# Accumulator_HotDog_v2.net
KiCad netlist of a schematic drawn in Altium Designer
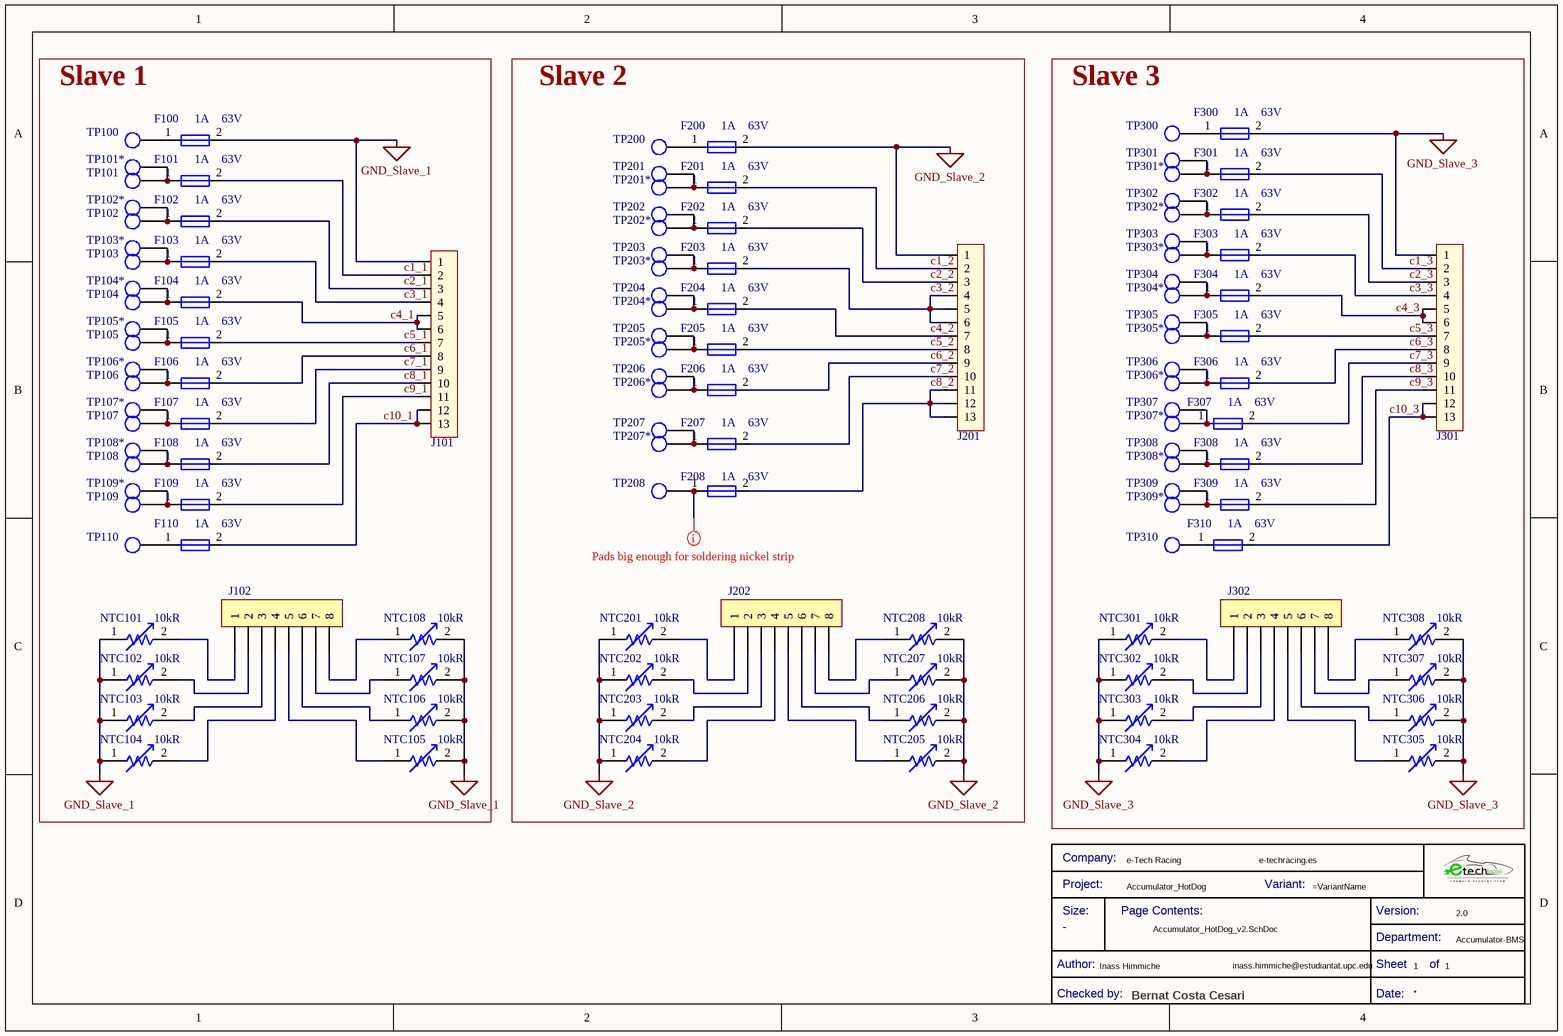
[diagram p0: Accumulator_HotDog_v2.SchDoc]

(export (version "E")
  (design (tool "Eeschema 10.0.6"))
  (components
    (comp (ref "*")
      (value "Title Block_template")
      (description "Standard Title Block")
      (fields (field (name "SIZE") "-"))
      (libsource (lib "e-Tech_Racing") (part "Title Block_template"))
    )
    (comp (ref "F100")
      (value "0437001.WRA")
      (footprint "Fuse_1206")
      (description "Fuse Chip Fast Acting 1A 63V SMD Solder Pad 1206 Ceramic T/R Automotive")
      (fields
        (field (name "MANUFACTURER") "Littelfuse")
        (field (name "CURRENT RATING") "1A")
        (field (name "VOLTAGE RATING (DC)") "63V")
      )
      (libsource (lib "Filter components") (part "Fuse_1A_63V_1206"))
    )
    (comp (ref "F101")
      (value "0437001.WRA")
      (footprint "Fuse_1206")
      (description "Fuse Chip Fast Acting 1A 63V SMD Solder Pad 1206 Ceramic T/R Automotive")
      (fields
        (field (name "MANUFACTURER") "Littelfuse")
        (field (name "CURRENT RATING") "1A")
        (field (name "VOLTAGE RATING (DC)") "63V")
      )
      (libsource (lib "Filter components") (part "Fuse_1A_63V_1206"))
    )
    (comp (ref "F102")
      (value "0437001.WRA")
      (footprint "Fuse_1206")
      (description "Fuse Chip Fast Acting 1A 63V SMD Solder Pad 1206 Ceramic T/R Automotive")
      (fields
        (field (name "MANUFACTURER") "Littelfuse")
        (field (name "CURRENT RATING") "1A")
        (field (name "VOLTAGE RATING (DC)") "63V")
      )
      (libsource (lib "Filter components") (part "Fuse_1A_63V_1206"))
    )
    (comp (ref "F103")
      (value "0437001.WRA")
      (footprint "Fuse_1206")
      (description "Fuse Chip Fast Acting 1A 63V SMD Solder Pad 1206 Ceramic T/R Automotive")
      (fields
        (field (name "MANUFACTURER") "Littelfuse")
        (field (name "CURRENT RATING") "1A")
        (field (name "VOLTAGE RATING (DC)") "63V")
      )
      (libsource (lib "Filter components") (part "Fuse_1A_63V_1206"))
    )
    (comp (ref "F104")
      (value "0437001.WRA")
      (footprint "Fuse_1206")
      (description "Fuse Chip Fast Acting 1A 63V SMD Solder Pad 1206 Ceramic T/R Automotive")
      (fields
        (field (name "MANUFACTURER") "Littelfuse")
        (field (name "CURRENT RATING") "1A")
        (field (name "VOLTAGE RATING (DC)") "63V")
      )
      (libsource (lib "Filter components") (part "Fuse_1A_63V_1206"))
    )
    (comp (ref "F105")
      (value "0437001.WRA")
      (footprint "Fuse_1206")
      (description "Fuse Chip Fast Acting 1A 63V SMD Solder Pad 1206 Ceramic T/R Automotive")
      (fields
        (field (name "MANUFACTURER") "Littelfuse")
        (field (name "CURRENT RATING") "1A")
        (field (name "VOLTAGE RATING (DC)") "63V")
      )
      (libsource (lib "Filter components") (part "Fuse_1A_63V_1206"))
    )
    (comp (ref "F106")
      (value "0437001.WRA")
      (footprint "Fuse_1206")
      (description "Fuse Chip Fast Acting 1A 63V SMD Solder Pad 1206 Ceramic T/R Automotive")
      (fields
        (field (name "MANUFACTURER") "Littelfuse")
        (field (name "CURRENT RATING") "1A")
        (field (name "VOLTAGE RATING (DC)") "63V")
      )
      (libsource (lib "Filter components") (part "Fuse_1A_63V_1206"))
    )
    (comp (ref "F107")
      (value "0437001.WRA")
      (footprint "Fuse_1206")
      (description "Fuse Chip Fast Acting 1A 63V SMD Solder Pad 1206 Ceramic T/R Automotive")
      (fields
        (field (name "MANUFACTURER") "Littelfuse")
        (field (name "CURRENT RATING") "1A")
        (field (name "VOLTAGE RATING (DC)") "63V")
      )
      (libsource (lib "Filter components") (part "Fuse_1A_63V_1206"))
    )
    (comp (ref "F108")
      (value "0437001.WRA")
      (footprint "Fuse_1206")
      (description "Fuse Chip Fast Acting 1A 63V SMD Solder Pad 1206 Ceramic T/R Automotive")
      (fields
        (field (name "MANUFACTURER") "Littelfuse")
        (field (name "CURRENT RATING") "1A")
        (field (name "VOLTAGE RATING (DC)") "63V")
      )
      (libsource (lib "Filter components") (part "Fuse_1A_63V_1206"))
    )
    (comp (ref "F109")
      (value "0437001.WRA")
      (footprint "Fuse_1206")
      (description "Fuse Chip Fast Acting 1A 63V SMD Solder Pad 1206 Ceramic T/R Automotive")
      (fields
        (field (name "MANUFACTURER") "Littelfuse")
        (field (name "CURRENT RATING") "1A")
        (field (name "VOLTAGE RATING (DC)") "63V")
      )
      (libsource (lib "Filter components") (part "Fuse_1A_63V_1206"))
    )
    (comp (ref "F110")
      (value "0437001.WRA")
      (footprint "Fuse_1206")
      (description "Fuse Chip Fast Acting 1A 63V SMD Solder Pad 1206 Ceramic T/R Automotive")
      (fields
        (field (name "MANUFACTURER") "Littelfuse")
        (field (name "CURRENT RATING") "1A")
        (field (name "VOLTAGE RATING (DC)") "63V")
      )
      (libsource (lib "Filter components") (part "Fuse_1A_63V_1206"))
    )
    (comp (ref "F200")
      (value "0437001.WRA")
      (footprint "Fuse_1206")
      (description "Fuse Chip Fast Acting 1A 63V SMD Solder Pad 1206 Ceramic T/R Automotive")
      (fields
        (field (name "MANUFACTURER") "Littelfuse")
        (field (name "CURRENT RATING") "1A")
        (field (name "VOLTAGE RATING (DC)") "63V")
      )
      (libsource (lib "Filter components") (part "Fuse_1A_63V_1206"))
    )
    (comp (ref "F201")
      (value "0437001.WRA")
      (footprint "Fuse_1206")
      (description "Fuse Chip Fast Acting 1A 63V SMD Solder Pad 1206 Ceramic T/R Automotive")
      (fields
        (field (name "MANUFACTURER") "Littelfuse")
        (field (name "CURRENT RATING") "1A")
        (field (name "VOLTAGE RATING (DC)") "63V")
      )
      (libsource (lib "Filter components") (part "Fuse_1A_63V_1206"))
    )
    (comp (ref "F202")
      (value "0437001.WRA")
      (footprint "Fuse_1206")
      (description "Fuse Chip Fast Acting 1A 63V SMD Solder Pad 1206 Ceramic T/R Automotive")
      (fields
        (field (name "MANUFACTURER") "Littelfuse")
        (field (name "CURRENT RATING") "1A")
        (field (name "VOLTAGE RATING (DC)") "63V")
      )
      (libsource (lib "Filter components") (part "Fuse_1A_63V_1206"))
    )
    (comp (ref "F203")
      (value "0437001.WRA")
      (footprint "Fuse_1206")
      (description "Fuse Chip Fast Acting 1A 63V SMD Solder Pad 1206 Ceramic T/R Automotive")
      (fields
        (field (name "MANUFACTURER") "Littelfuse")
        (field (name "CURRENT RATING") "1A")
        (field (name "VOLTAGE RATING (DC)") "63V")
      )
      (libsource (lib "Filter components") (part "Fuse_1A_63V_1206"))
    )
    (comp (ref "F204")
      (value "0437001.WRA")
      (footprint "Fuse_1206")
      (description "Fuse Chip Fast Acting 1A 63V SMD Solder Pad 1206 Ceramic T/R Automotive")
      (fields
        (field (name "MANUFACTURER") "Littelfuse")
        (field (name "CURRENT RATING") "1A")
        (field (name "VOLTAGE RATING (DC)") "63V")
      )
      (libsource (lib "Filter components") (part "Fuse_1A_63V_1206"))
    )
    (comp (ref "F205")
      (value "0437001.WRA")
      (footprint "Fuse_1206")
      (description "Fuse Chip Fast Acting 1A 63V SMD Solder Pad 1206 Ceramic T/R Automotive")
      (fields
        (field (name "MANUFACTURER") "Littelfuse")
        (field (name "CURRENT RATING") "1A")
        (field (name "VOLTAGE RATING (DC)") "63V")
      )
      (libsource (lib "Filter components") (part "Fuse_1A_63V_1206"))
    )
    (comp (ref "F206")
      (value "0437001.WRA")
      (footprint "Fuse_1206")
      (description "Fuse Chip Fast Acting 1A 63V SMD Solder Pad 1206 Ceramic T/R Automotive")
      (fields
        (field (name "MANUFACTURER") "Littelfuse")
        (field (name "CURRENT RATING") "1A")
        (field (name "VOLTAGE RATING (DC)") "63V")
      )
      (libsource (lib "Filter components") (part "Fuse_1A_63V_1206"))
    )
    (comp (ref "F207")
      (value "0437001.WRA")
      (footprint "Fuse_1206")
      (description "Fuse Chip Fast Acting 1A 63V SMD Solder Pad 1206 Ceramic T/R Automotive")
      (fields
        (field (name "MANUFACTURER") "Littelfuse")
        (field (name "CURRENT RATING") "1A")
        (field (name "VOLTAGE RATING (DC)") "63V")
      )
      (libsource (lib "Filter components") (part "Fuse_1A_63V_1206"))
    )
    (comp (ref "F208")
      (value "0437001.WRA")
      (footprint "Fuse_1206")
      (description "Fuse Chip Fast Acting 1A 63V SMD Solder Pad 1206 Ceramic T/R Automotive")
      (fields
        (field (name "MANUFACTURER") "Littelfuse")
        (field (name "CURRENT RATING") "1A")
        (field (name "VOLTAGE RATING (DC)") "63V")
      )
      (libsource (lib "Filter components") (part "Fuse_1A_63V_1206"))
    )
    (comp (ref "F300")
      (value "0437001.WRA")
      (footprint "Fuse_1206")
      (description "Fuse Chip Fast Acting 1A 63V SMD Solder Pad 1206 Ceramic T/R Automotive")
      (fields
        (field (name "MANUFACTURER") "Littelfuse")
        (field (name "CURRENT RATING") "1A")
        (field (name "VOLTAGE RATING (DC)") "63V")
      )
      (libsource (lib "Filter components") (part "Fuse_1A_63V_1206"))
    )
    (comp (ref "F301")
      (value "0437001.WRA")
      (footprint "Fuse_1206")
      (description "Fuse Chip Fast Acting 1A 63V SMD Solder Pad 1206 Ceramic T/R Automotive")
      (fields
        (field (name "MANUFACTURER") "Littelfuse")
        (field (name "CURRENT RATING") "1A")
        (field (name "VOLTAGE RATING (DC)") "63V")
      )
      (libsource (lib "Filter components") (part "Fuse_1A_63V_1206"))
    )
    (comp (ref "F302")
      (value "0437001.WRA")
      (footprint "Fuse_1206")
      (description "Fuse Chip Fast Acting 1A 63V SMD Solder Pad 1206 Ceramic T/R Automotive")
      (fields
        (field (name "MANUFACTURER") "Littelfuse")
        (field (name "CURRENT RATING") "1A")
        (field (name "VOLTAGE RATING (DC)") "63V")
      )
      (libsource (lib "Filter components") (part "Fuse_1A_63V_1206"))
    )
    (comp (ref "F303")
      (value "0437001.WRA")
      (footprint "Fuse_1206")
      (description "Fuse Chip Fast Acting 1A 63V SMD Solder Pad 1206 Ceramic T/R Automotive")
      (fields
        (field (name "MANUFACTURER") "Littelfuse")
        (field (name "CURRENT RATING") "1A")
        (field (name "VOLTAGE RATING (DC)") "63V")
      )
      (libsource (lib "Filter components") (part "Fuse_1A_63V_1206"))
    )
    (comp (ref "F304")
      (value "0437001.WRA")
      (footprint "Fuse_1206")
      (description "Fuse Chip Fast Acting 1A 63V SMD Solder Pad 1206 Ceramic T/R Automotive")
      (fields
        (field (name "MANUFACTURER") "Littelfuse")
        (field (name "CURRENT RATING") "1A")
        (field (name "VOLTAGE RATING (DC)") "63V")
      )
      (libsource (lib "Filter components") (part "Fuse_1A_63V_1206"))
    )
    (comp (ref "F305")
      (value "0437001.WRA")
      (footprint "Fuse_1206")
      (description "Fuse Chip Fast Acting 1A 63V SMD Solder Pad 1206 Ceramic T/R Automotive")
      (fields
        (field (name "MANUFACTURER") "Littelfuse")
        (field (name "CURRENT RATING") "1A")
        (field (name "VOLTAGE RATING (DC)") "63V")
      )
      (libsource (lib "Filter components") (part "Fuse_1A_63V_1206"))
    )
    (comp (ref "F306")
      (value "0437001.WRA")
      (footprint "Fuse_1206")
      (description "Fuse Chip Fast Acting 1A 63V SMD Solder Pad 1206 Ceramic T/R Automotive")
      (fields
        (field (name "MANUFACTURER") "Littelfuse")
        (field (name "CURRENT RATING") "1A")
        (field (name "VOLTAGE RATING (DC)") "63V")
      )
      (libsource (lib "Filter components") (part "Fuse_1A_63V_1206"))
    )
    (comp (ref "F307")
      (value "0437001.WRA")
      (footprint "Fuse_1206")
      (description "Fuse Chip Fast Acting 1A 63V SMD Solder Pad 1206 Ceramic T/R Automotive")
      (fields
        (field (name "MANUFACTURER") "Littelfuse")
        (field (name "CURRENT RATING") "1A")
        (field (name "VOLTAGE RATING (DC)") "63V")
      )
      (libsource (lib "Filter components") (part "Fuse_1A_63V_1206"))
    )
    (comp (ref "F308")
      (value "0437001.WRA")
      (footprint "Fuse_1206")
      (description "Fuse Chip Fast Acting 1A 63V SMD Solder Pad 1206 Ceramic T/R Automotive")
      (fields
        (field (name "MANUFACTURER") "Littelfuse")
        (field (name "CURRENT RATING") "1A")
        (field (name "VOLTAGE RATING (DC)") "63V")
      )
      (libsource (lib "Filter components") (part "Fuse_1A_63V_1206"))
    )
    (comp (ref "F309")
      (value "0437001.WRA")
      (footprint "Fuse_1206")
      (description "Fuse Chip Fast Acting 1A 63V SMD Solder Pad 1206 Ceramic T/R Automotive")
      (fields
        (field (name "MANUFACTURER") "Littelfuse")
        (field (name "CURRENT RATING") "1A")
        (field (name "VOLTAGE RATING (DC)") "63V")
      )
      (libsource (lib "Filter components") (part "Fuse_1A_63V_1206"))
    )
    (comp (ref "F310")
      (value "0437001.WRA")
      (footprint "Fuse_1206")
      (description "Fuse Chip Fast Acting 1A 63V SMD Solder Pad 1206 Ceramic T/R Automotive")
      (fields
        (field (name "MANUFACTURER") "Littelfuse")
        (field (name "CURRENT RATING") "1A")
        (field (name "VOLTAGE RATING (DC)") "63V")
      )
      (libsource (lib "Filter components") (part "Fuse_1A_63V_1206"))
    )
    (comp (ref "J101")
      (value "WR-PHD 13 socket header")
      (footprint "61301311821")
      (description "13 pin Socket Header 61301311821")
      (libsource (lib "Electromechanical") (part "J_WR-PHD 13pin Socket Header"))
    )
    (comp (ref "J102")
      (value "J_WR-PHD 8pin Socket Header")
      (footprint "61300811821")
      (description "8pin Socket Header 2.54 mm")
      (libsource (lib "Electromechanical") (part "J_WR-PHD 8pin Socket Header"))
    )
    (comp (ref "J201")
      (value "WR-PHD 13 socket header")
      (footprint "61301311821")
      (description "13 pin Socket Header 61301311821")
      (libsource (lib "Electromechanical") (part "J_WR-PHD 13pin Socket Header"))
    )
    (comp (ref "J202")
      (value "J_WR-PHD 8pin Socket Header")
      (footprint "61300811821")
      (description "8pin Socket Header 2.54 mm")
      (libsource (lib "Electromechanical") (part "J_WR-PHD 8pin Socket Header"))
    )
    (comp (ref "J301")
      (value "WR-PHD 13 socket header")
      (footprint "61301311821")
      (description "13 pin Socket Header 61301311821")
      (libsource (lib "Electromechanical") (part "J_WR-PHD 13pin Socket Header"))
    )
    (comp (ref "J302")
      (value "J_WR-PHD 8pin Socket Header")
      (footprint "61300811821")
      (description "8pin Socket Header 2.54 mm")
      (libsource (lib "Electromechanical") (part "J_WR-PHD 8pin Socket Header"))
    )
    (comp (ref "NTC101")
      (value "NXRT15XV103FA1B040")
      (footprint "NTC_NXRT15XV103FA1B040")
      (description "NXR Series 10 kOhm 3900 K ±1% Bead NTC Thermistor Sensor")
      (fields (field (name "TOLERANCE") "1%") (field (name "RESISTANCE") "10kR"))
      (libsource (lib "Sensors") (part "NTC_NXRT15XV103FA1B040"))
    )
    (comp (ref "NTC102")
      (value "NXRT15XV103FA1B040")
      (footprint "NTC_NXRT15XV103FA1B040")
      (description "NXR Series 10 kOhm 3900 K ±1% Bead NTC Thermistor Sensor")
      (fields (field (name "TOLERANCE") "1%") (field (name "RESISTANCE") "10kR"))
      (libsource (lib "Sensors") (part "NTC_NXRT15XV103FA1B040"))
    )
    (comp (ref "NTC103")
      (value "NXRT15XV103FA1B040")
      (footprint "NTC_NXRT15XV103FA1B040")
      (description "NXR Series 10 kOhm 3900 K ±1% Bead NTC Thermistor Sensor")
      (fields (field (name "TOLERANCE") "1%") (field (name "RESISTANCE") "10kR"))
      (libsource (lib "Sensors") (part "NTC_NXRT15XV103FA1B040"))
    )
    (comp (ref "NTC104")
      (value "NXRT15XV103FA1B040")
      (footprint "NTC_NXRT15XV103FA1B040")
      (description "NXR Series 10 kOhm 3900 K ±1% Bead NTC Thermistor Sensor")
      (fields (field (name "TOLERANCE") "1%") (field (name "RESISTANCE") "10kR"))
      (libsource (lib "Sensors") (part "NTC_NXRT15XV103FA1B040"))
    )
    (comp (ref "NTC105")
      (value "NXRT15XV103FA1B040")
      (footprint "NTC_NXRT15XV103FA1B040")
      (description "NXR Series 10 kOhm 3900 K ±1% Bead NTC Thermistor Sensor")
      (fields (field (name "TOLERANCE") "1%") (field (name "RESISTANCE") "10kR"))
      (libsource (lib "Sensors") (part "NTC_NXRT15XV103FA1B040"))
    )
    (comp (ref "NTC106")
      (value "NXRT15XV103FA1B040")
      (footprint "NTC_NXRT15XV103FA1B040")
      (description "NXR Series 10 kOhm 3900 K ±1% Bead NTC Thermistor Sensor")
      (fields (field (name "TOLERANCE") "1%") (field (name "RESISTANCE") "10kR"))
      (libsource (lib "Sensors") (part "NTC_NXRT15XV103FA1B040"))
    )
    (comp (ref "NTC107")
      (value "NXRT15XV103FA1B040")
      (footprint "NTC_NXRT15XV103FA1B040")
      (description "NXR Series 10 kOhm 3900 K ±1% Bead NTC Thermistor Sensor")
      (fields (field (name "TOLERANCE") "1%") (field (name "RESISTANCE") "10kR"))
      (libsource (lib "Sensors") (part "NTC_NXRT15XV103FA1B040"))
    )
    (comp (ref "NTC108")
      (value "NXRT15XV103FA1B040")
      (footprint "NTC_NXRT15XV103FA1B040")
      (description "NXR Series 10 kOhm 3900 K ±1% Bead NTC Thermistor Sensor")
      (fields (field (name "TOLERANCE") "1%") (field (name "RESISTANCE") "10kR"))
      (libsource (lib "Sensors") (part "NTC_NXRT15XV103FA1B040"))
    )
    (comp (ref "NTC201")
      (value "NXRT15XV103FA1B040")
      (footprint "NTC_NXRT15XV103FA1B040")
      (description "NXR Series 10 kOhm 3900 K ±1% Bead NTC Thermistor Sensor")
      (fields (field (name "TOLERANCE") "1%") (field (name "RESISTANCE") "10kR"))
      (libsource (lib "Sensors") (part "NTC_NXRT15XV103FA1B040"))
    )
    (comp (ref "NTC202")
      (value "NXRT15XV103FA1B040")
      (footprint "NTC_NXRT15XV103FA1B040")
      (description "NXR Series 10 kOhm 3900 K ±1% Bead NTC Thermistor Sensor")
      (fields (field (name "TOLERANCE") "1%") (field (name "RESISTANCE") "10kR"))
      (libsource (lib "Sensors") (part "NTC_NXRT15XV103FA1B040"))
    )
    (comp (ref "NTC203")
      (value "NXRT15XV103FA1B040")
      (footprint "NTC_NXRT15XV103FA1B040")
      (description "NXR Series 10 kOhm 3900 K ±1% Bead NTC Thermistor Sensor")
      (fields (field (name "TOLERANCE") "1%") (field (name "RESISTANCE") "10kR"))
      (libsource (lib "Sensors") (part "NTC_NXRT15XV103FA1B040"))
    )
    (comp (ref "NTC204")
      (value "NXRT15XV103FA1B040")
      (footprint "NTC_NXRT15XV103FA1B040")
      (description "NXR Series 10 kOhm 3900 K ±1% Bead NTC Thermistor Sensor")
      (fields (field (name "TOLERANCE") "1%") (field (name "RESISTANCE") "10kR"))
      (libsource (lib "Sensors") (part "NTC_NXRT15XV103FA1B040"))
    )
    (comp (ref "NTC205")
      (value "NXRT15XV103FA1B040")
      (footprint "NTC_NXRT15XV103FA1B040")
      (description "NXR Series 10 kOhm 3900 K ±1% Bead NTC Thermistor Sensor")
      (fields (field (name "TOLERANCE") "1%") (field (name "RESISTANCE") "10kR"))
      (libsource (lib "Sensors") (part "NTC_NXRT15XV103FA1B040"))
    )
    (comp (ref "NTC206")
      (value "NXRT15XV103FA1B040")
      (footprint "NTC_NXRT15XV103FA1B040")
      (description "NXR Series 10 kOhm 3900 K ±1% Bead NTC Thermistor Sensor")
      (fields (field (name "TOLERANCE") "1%") (field (name "RESISTANCE") "10kR"))
      (libsource (lib "Sensors") (part "NTC_NXRT15XV103FA1B040"))
    )
    (comp (ref "NTC207")
      (value "NXRT15XV103FA1B040")
      (footprint "NTC_NXRT15XV103FA1B040")
      (description "NXR Series 10 kOhm 3900 K ±1% Bead NTC Thermistor Sensor")
      (fields (field (name "TOLERANCE") "1%") (field (name "RESISTANCE") "10kR"))
      (libsource (lib "Sensors") (part "NTC_NXRT15XV103FA1B040"))
    )
    (comp (ref "NTC208")
      (value "NXRT15XV103FA1B040")
      (footprint "NTC_NXRT15XV103FA1B040")
      (description "NXR Series 10 kOhm 3900 K ±1% Bead NTC Thermistor Sensor")
      (fields (field (name "TOLERANCE") "1%") (field (name "RESISTANCE") "10kR"))
      (libsource (lib "Sensors") (part "NTC_NXRT15XV103FA1B040"))
    )
    (comp (ref "NTC301")
      (value "NXRT15XV103FA1B040")
      (footprint "NTC_NXRT15XV103FA1B040")
      (description "NXR Series 10 kOhm 3900 K ±1% Bead NTC Thermistor Sensor")
      (fields (field (name "TOLERANCE") "1%") (field (name "RESISTANCE") "10kR"))
      (libsource (lib "Sensors") (part "NTC_NXRT15XV103FA1B040"))
    )
    (comp (ref "NTC302")
      (value "NXRT15XV103FA1B040")
      (footprint "NTC_NXRT15XV103FA1B040")
      (description "NXR Series 10 kOhm 3900 K ±1% Bead NTC Thermistor Sensor")
      (fields (field (name "TOLERANCE") "1%") (field (name "RESISTANCE") "10kR"))
      (libsource (lib "Sensors") (part "NTC_NXRT15XV103FA1B040"))
    )
    (comp (ref "NTC303")
      (value "NXRT15XV103FA1B040")
      (footprint "NTC_NXRT15XV103FA1B040")
      (description "NXR Series 10 kOhm 3900 K ±1% Bead NTC Thermistor Sensor")
      (fields (field (name "TOLERANCE") "1%") (field (name "RESISTANCE") "10kR"))
      (libsource (lib "Sensors") (part "NTC_NXRT15XV103FA1B040"))
    )
    (comp (ref "NTC304")
      (value "NXRT15XV103FA1B040")
      (footprint "NTC_NXRT15XV103FA1B040")
      (description "NXR Series 10 kOhm 3900 K ±1% Bead NTC Thermistor Sensor")
      (fields (field (name "TOLERANCE") "1%") (field (name "RESISTANCE") "10kR"))
      (libsource (lib "Sensors") (part "NTC_NXRT15XV103FA1B040"))
    )
    (comp (ref "NTC305")
      (value "NXRT15XV103FA1B040")
      (footprint "NTC_NXRT15XV103FA1B040")
      (description "NXR Series 10 kOhm 3900 K ±1% Bead NTC Thermistor Sensor")
      (fields (field (name "TOLERANCE") "1%") (field (name "RESISTANCE") "10kR"))
      (libsource (lib "Sensors") (part "NTC_NXRT15XV103FA1B040"))
    )
    (comp (ref "NTC306")
      (value "NXRT15XV103FA1B040")
      (footprint "NTC_NXRT15XV103FA1B040")
      (description "NXR Series 10 kOhm 3900 K ±1% Bead NTC Thermistor Sensor")
      (fields (field (name "TOLERANCE") "1%") (field (name "RESISTANCE") "10kR"))
      (libsource (lib "Sensors") (part "NTC_NXRT15XV103FA1B040"))
    )
    (comp (ref "NTC307")
      (value "NXRT15XV103FA1B040")
      (footprint "NTC_NXRT15XV103FA1B040")
      (description "NXR Series 10 kOhm 3900 K ±1% Bead NTC Thermistor Sensor")
      (fields (field (name "TOLERANCE") "1%") (field (name "RESISTANCE") "10kR"))
      (libsource (lib "Sensors") (part "NTC_NXRT15XV103FA1B040"))
    )
    (comp (ref "NTC308")
      (value "NXRT15XV103FA1B040")
      (footprint "NTC_NXRT15XV103FA1B040")
      (description "NXR Series 10 kOhm 3900 K ±1% Bead NTC Thermistor Sensor")
      (fields (field (name "TOLERANCE") "1%") (field (name "RESISTANCE") "10kR"))
      (libsource (lib "Sensors") (part "NTC_NXRT15XV103FA1B040"))
    )
    (comp (ref "TP100")
      (value "TestPoint")
      (footprint "TestPoint")
      (description "Test Point 1x1 mm")
      (libsource (lib "e-Tech_Racing") (part "TestPoint"))
    )
    (comp (ref "TP101")
      (value "TestPoint")
      (footprint "TestPoint")
      (description "Test Point 1x1 mm")
      (libsource (lib "e-Tech_Racing") (part "TestPoint"))
    )
    (comp (ref "TP101*")
      (value "TestPoint")
      (footprint "TestPoint")
      (description "Test Point 1x1 mm")
      (libsource (lib "e-Tech_Racing") (part "TestPoint"))
    )
    (comp (ref "TP102")
      (value "TestPoint")
      (footprint "TestPoint")
      (description "Test Point 1x1 mm")
      (libsource (lib "e-Tech_Racing") (part "TestPoint"))
    )
    (comp (ref "TP102*")
      (value "TestPoint")
      (footprint "TestPoint")
      (description "Test Point 1x1 mm")
      (libsource (lib "e-Tech_Racing") (part "TestPoint"))
    )
    (comp (ref "TP103")
      (value "TestPoint")
      (footprint "TestPoint")
      (description "Test Point 1x1 mm")
      (libsource (lib "e-Tech_Racing") (part "TestPoint"))
    )
    (comp (ref "TP103*")
      (value "TestPoint")
      (footprint "TestPoint")
      (description "Test Point 1x1 mm")
      (libsource (lib "e-Tech_Racing") (part "TestPoint"))
    )
    (comp (ref "TP104")
      (value "TestPoint")
      (footprint "TestPoint")
      (description "Test Point 1x1 mm")
      (libsource (lib "e-Tech_Racing") (part "TestPoint"))
    )
    (comp (ref "TP104*")
      (value "TestPoint")
      (footprint "TestPoint")
      (description "Test Point 1x1 mm")
      (libsource (lib "e-Tech_Racing") (part "TestPoint"))
    )
    (comp (ref "TP105")
      (value "TestPoint")
      (footprint "TestPoint")
      (description "Test Point 1x1 mm")
      (libsource (lib "e-Tech_Racing") (part "TestPoint"))
    )
    (comp (ref "TP105*")
      (value "TestPoint")
      (footprint "TestPoint")
      (description "Test Point 1x1 mm")
      (libsource (lib "e-Tech_Racing") (part "TestPoint"))
    )
    (comp (ref "TP106")
      (value "TestPoint")
      (footprint "TestPoint")
      (description "Test Point 1x1 mm")
      (libsource (lib "e-Tech_Racing") (part "TestPoint"))
    )
    (comp (ref "TP106*")
      (value "TestPoint")
      (footprint "TestPoint")
      (description "Test Point 1x1 mm")
      (libsource (lib "e-Tech_Racing") (part "TestPoint"))
    )
    (comp (ref "TP107")
      (value "TestPoint")
      (footprint "TestPoint")
      (description "Test Point 1x1 mm")
      (libsource (lib "e-Tech_Racing") (part "TestPoint"))
    )
    (comp (ref "TP107*")
      (value "TestPoint")
      (footprint "TestPoint")
      (description "Test Point 1x1 mm")
      (libsource (lib "e-Tech_Racing") (part "TestPoint"))
    )
    (comp (ref "TP108")
      (value "TestPoint")
      (footprint "TestPoint")
      (description "Test Point 1x1 mm")
      (libsource (lib "e-Tech_Racing") (part "TestPoint"))
    )
    (comp (ref "TP108*")
      (value "TestPoint")
      (footprint "TestPoint")
      (description "Test Point 1x1 mm")
      (libsource (lib "e-Tech_Racing") (part "TestPoint"))
    )
    (comp (ref "TP109")
      (value "TestPoint")
      (footprint "TestPoint")
      (description "Test Point 1x1 mm")
      (libsource (lib "e-Tech_Racing") (part "TestPoint"))
    )
    (comp (ref "TP109*")
      (value "TestPoint")
      (footprint "TestPoint")
      (description "Test Point 1x1 mm")
      (libsource (lib "e-Tech_Racing") (part "TestPoint"))
    )
    (comp (ref "TP110")
      (value "TestPoint")
      (footprint "TestPoint")
      (description "Test Point 1x1 mm")
      (libsource (lib "e-Tech_Racing") (part "TestPoint"))
    )
    (comp (ref "TP200")
      (value "TestPoint")
      (footprint "TestPoint")
      (description "Test Point 1x1 mm")
      (libsource (lib "e-Tech_Racing") (part "TestPoint"))
    )
    (comp (ref "TP201")
      (value "TestPoint")
      (footprint "TestPoint")
      (description "Test Point 1x1 mm")
      (libsource (lib "e-Tech_Racing") (part "TestPoint"))
    )
    (comp (ref "TP201*")
      (value "TestPoint")
      (footprint "TestPoint")
      (description "Test Point 1x1 mm")
      (libsource (lib "e-Tech_Racing") (part "TestPoint"))
    )
    (comp (ref "TP202")
      (value "TestPoint")
      (footprint "TestPoint")
      (description "Test Point 1x1 mm")
      (libsource (lib "e-Tech_Racing") (part "TestPoint"))
    )
    (comp (ref "TP202*")
      (value "TestPoint")
      (footprint "TestPoint")
      (description "Test Point 1x1 mm")
      (libsource (lib "e-Tech_Racing") (part "TestPoint"))
    )
    (comp (ref "TP203")
      (value "TestPoint")
      (footprint "TestPoint")
      (description "Test Point 1x1 mm")
      (libsource (lib "e-Tech_Racing") (part "TestPoint"))
    )
    (comp (ref "TP203*")
      (value "TestPoint")
      (footprint "TestPoint")
      (description "Test Point 1x1 mm")
      (libsource (lib "e-Tech_Racing") (part "TestPoint"))
    )
    (comp (ref "TP204")
      (value "TestPoint")
      (footprint "TestPoint")
      (description "Test Point 1x1 mm")
      (libsource (lib "e-Tech_Racing") (part "TestPoint"))
    )
    (comp (ref "TP204*")
      (value "TestPoint")
      (footprint "TestPoint")
      (description "Test Point 1x1 mm")
      (libsource (lib "e-Tech_Racing") (part "TestPoint"))
    )
    (comp (ref "TP205")
      (value "TestPoint")
      (footprint "TestPoint")
      (description "Test Point 1x1 mm")
      (libsource (lib "e-Tech_Racing") (part "TestPoint"))
    )
    (comp (ref "TP205*")
      (value "TestPoint")
      (footprint "TestPoint")
      (description "Test Point 1x1 mm")
      (libsource (lib "e-Tech_Racing") (part "TestPoint"))
    )
    (comp (ref "TP206")
      (value "TestPoint")
      (footprint "TestPoint")
      (description "Test Point 1x1 mm")
      (libsource (lib "e-Tech_Racing") (part "TestPoint"))
    )
    (comp (ref "TP206*")
      (value "TestPoint")
      (footprint "TestPoint")
      (description "Test Point 1x1 mm")
      (libsource (lib "e-Tech_Racing") (part "TestPoint"))
    )
    (comp (ref "TP207")
      (value "TestPoint")
      (footprint "TestPoint")
      (description "Test Point 1x1 mm")
      (libsource (lib "e-Tech_Racing") (part "TestPoint"))
    )
    (comp (ref "TP207*")
      (value "TestPoint")
      (footprint "TestPoint")
      (description "Test Point 1x1 mm")
      (libsource (lib "e-Tech_Racing") (part "TestPoint"))
    )
    (comp (ref "TP208")
      (value "TestPoint")
      (footprint "TestPoint")
      (description "Test Point 1x1 mm")
      (libsource (lib "e-Tech_Racing") (part "TestPoint"))
    )
    (comp (ref "TP300")
      (value "TestPoint")
      (footprint "TestPoint")
      (description "Test Point 1x1 mm")
      (libsource (lib "e-Tech_Racing") (part "TestPoint"))
    )
    (comp (ref "TP301")
      (value "TestPoint")
      (footprint "TestPoint")
      (description "Test Point 1x1 mm")
      (libsource (lib "e-Tech_Racing") (part "TestPoint"))
    )
    (comp (ref "TP301*")
      (value "TestPoint")
      (footprint "TestPoint")
      (description "Test Point 1x1 mm")
      (libsource (lib "e-Tech_Racing") (part "TestPoint"))
    )
    (comp (ref "TP302")
      (value "TestPoint")
      (footprint "TestPoint")
      (description "Test Point 1x1 mm")
      (libsource (lib "e-Tech_Racing") (part "TestPoint"))
    )
    (comp (ref "TP302*")
      (value "TestPoint")
      (footprint "TestPoint")
      (description "Test Point 1x1 mm")
      (libsource (lib "e-Tech_Racing") (part "TestPoint"))
    )
    (comp (ref "TP303")
      (value "TestPoint")
      (footprint "TestPoint")
      (description "Test Point 1x1 mm")
      (libsource (lib "e-Tech_Racing") (part "TestPoint"))
    )
    (comp (ref "TP303*")
      (value "TestPoint")
      (footprint "TestPoint")
      (description "Test Point 1x1 mm")
      (libsource (lib "e-Tech_Racing") (part "TestPoint"))
    )
    (comp (ref "TP304")
      (value "TestPoint")
      (footprint "TestPoint")
      (description "Test Point 1x1 mm")
      (libsource (lib "e-Tech_Racing") (part "TestPoint"))
    )
    (comp (ref "TP304*")
      (value "TestPoint")
      (footprint "TestPoint")
      (description "Test Point 1x1 mm")
      (libsource (lib "e-Tech_Racing") (part "TestPoint"))
    )
    (comp (ref "TP305")
      (value "TestPoint")
      (footprint "TestPoint")
      (description "Test Point 1x1 mm")
      (libsource (lib "e-Tech_Racing") (part "TestPoint"))
    )
    (comp (ref "TP305*")
      (value "TestPoint")
      (footprint "TestPoint")
      (description "Test Point 1x1 mm")
      (libsource (lib "e-Tech_Racing") (part "TestPoint"))
    )
    (comp (ref "TP306")
      (value "TestPoint")
      (footprint "TestPoint")
      (description "Test Point 1x1 mm")
      (libsource (lib "e-Tech_Racing") (part "TestPoint"))
    )
    (comp (ref "TP306*")
      (value "TestPoint")
      (footprint "TestPoint")
      (description "Test Point 1x1 mm")
      (libsource (lib "e-Tech_Racing") (part "TestPoint"))
    )
    (comp (ref "TP307")
      (value "TestPoint")
      (footprint "TestPoint")
      (description "Test Point 1x1 mm")
      (libsource (lib "e-Tech_Racing") (part "TestPoint"))
    )
    (comp (ref "TP307*")
      (value "TestPoint")
      (footprint "TestPoint")
      (description "Test Point 1x1 mm")
      (libsource (lib "e-Tech_Racing") (part "TestPoint"))
    )
    (comp (ref "TP308")
      (value "TestPoint")
      (footprint "TestPoint")
      (description "Test Point 1x1 mm")
      (libsource (lib "e-Tech_Racing") (part "TestPoint"))
    )
    (comp (ref "TP308*")
      (value "TestPoint")
      (footprint "TestPoint")
      (description "Test Point 1x1 mm")
      (libsource (lib "e-Tech_Racing") (part "TestPoint"))
    )
    (comp (ref "TP309")
      (value "TestPoint")
      (footprint "TestPoint")
      (description "Test Point 1x1 mm")
      (libsource (lib "e-Tech_Racing") (part "TestPoint"))
    )
    (comp (ref "TP309*")
      (value "TestPoint")
      (footprint "TestPoint")
      (description "Test Point 1x1 mm")
      (libsource (lib "e-Tech_Racing") (part "TestPoint"))
    )
    (comp (ref "TP310")
      (value "TestPoint")
      (footprint "TestPoint")
      (description "Test Point 1x1 mm")
      (libsource (lib "e-Tech_Racing") (part "TestPoint"))
    )
  )
  (nets
    (net (code "1") (name "/c1_1") (class "Default")
      (node (ref "F101") (pin "2") (pinfunction "2_2") (pintype "passive"))
      (node (ref "J101") (pin "2") (pinfunction "2_2") (pintype "passive"))
    )
    (net (code "2") (name "/c1_2") (class "Default")
      (node (ref "F201") (pin "2") (pinfunction "2_2") (pintype "passive"))
      (node (ref "J201") (pin "2") (pinfunction "2_2") (pintype "passive"))
    )
    (net (code "3") (name "/c1_3") (class "Default")
      (node (ref "F301") (pin "2") (pinfunction "2_2") (pintype "passive"))
      (node (ref "J301") (pin "2") (pinfunction "2_2") (pintype "passive"))
    )
    (net (code "4") (name "/c2_1") (class "Default")
      (node (ref "F102") (pin "2") (pinfunction "2_2") (pintype "passive"))
      (node (ref "J101") (pin "3") (pinfunction "3_3") (pintype "passive"))
    )
    (net (code "5") (name "/c2_2") (class "Default")
      (node (ref "F202") (pin "2") (pinfunction "2_2") (pintype "passive"))
      (node (ref "J201") (pin "3") (pinfunction "3_3") (pintype "passive"))
    )
    (net (code "6") (name "/c2_3") (class "Default")
      (node (ref "F302") (pin "2") (pinfunction "2_2") (pintype "passive"))
      (node (ref "J301") (pin "3") (pinfunction "3_3") (pintype "passive"))
    )
    (net (code "7") (name "/c3_1") (class "Default")
      (node (ref "F103") (pin "2") (pinfunction "2_2") (pintype "passive"))
      (node (ref "J101") (pin "4") (pinfunction "4_4") (pintype "passive"))
    )
    (net (code "8") (name "/c3_2") (class "Default")
      (node (ref "F203") (pin "2") (pinfunction "2_2") (pintype "passive"))
      (node (ref "J201") (pin "4") (pinfunction "4_4") (pintype "passive"))
      (node (ref "J201") (pin "5") (pinfunction "5_5") (pintype "passive"))
      (node (ref "J201") (pin "6") (pinfunction "6_6") (pintype "passive"))
    )
    (net (code "9") (name "/c3_3") (class "Default")
      (node (ref "F303") (pin "2") (pinfunction "2_2") (pintype "passive"))
      (node (ref "J301") (pin "4") (pinfunction "4_4") (pintype "passive"))
    )
    (net (code "10") (name "/c4_1") (class "Default")
      (node (ref "F104") (pin "2") (pinfunction "2_2") (pintype "passive"))
      (node (ref "J101") (pin "5") (pinfunction "5_5") (pintype "passive"))
      (node (ref "J101") (pin "6") (pinfunction "6_6") (pintype "passive"))
    )
    (net (code "11") (name "/c4_2") (class "Default")
      (node (ref "F204") (pin "2") (pinfunction "2_2") (pintype "passive"))
      (node (ref "J201") (pin "7") (pinfunction "7_7") (pintype "passive"))
    )
    (net (code "12") (name "/c4_3") (class "Default")
      (node (ref "F304") (pin "2") (pinfunction "2_2") (pintype "passive"))
      (node (ref "J301") (pin "5") (pinfunction "5_5") (pintype "passive"))
      (node (ref "J301") (pin "6") (pinfunction "6_6") (pintype "passive"))
    )
    (net (code "13") (name "/c5_1") (class "Default")
      (node (ref "F105") (pin "2") (pinfunction "2_2") (pintype "passive"))
      (node (ref "J101") (pin "7") (pinfunction "7_7") (pintype "passive"))
    )
    (net (code "14") (name "/c5_2") (class "Default")
      (node (ref "F205") (pin "2") (pinfunction "2_2") (pintype "passive"))
      (node (ref "J201") (pin "8") (pinfunction "8_8") (pintype "passive"))
    )
    (net (code "15") (name "/c5_3") (class "Default")
      (node (ref "F305") (pin "2") (pinfunction "2_2") (pintype "passive"))
      (node (ref "J301") (pin "7") (pinfunction "7_7") (pintype "passive"))
    )
    (net (code "16") (name "/c6_1") (class "Default")
      (node (ref "F106") (pin "2") (pinfunction "2_2") (pintype "passive"))
      (node (ref "J101") (pin "8") (pinfunction "8_8") (pintype "passive"))
    )
    (net (code "17") (name "/c6_2") (class "Default")
      (node (ref "F206") (pin "2") (pinfunction "2_2") (pintype "passive"))
      (node (ref "J201") (pin "9") (pinfunction "9_9") (pintype "passive"))
    )
    (net (code "18") (name "/c6_3") (class "Default")
      (node (ref "F306") (pin "2") (pinfunction "2_2") (pintype "passive"))
      (node (ref "J301") (pin "8") (pinfunction "8_8") (pintype "passive"))
    )
    (net (code "19") (name "/c7_1") (class "Default")
      (node (ref "F107") (pin "2") (pinfunction "2_2") (pintype "passive"))
      (node (ref "J101") (pin "9") (pinfunction "9_9") (pintype "passive"))
    )
    (net (code "20") (name "/c7_2") (class "Default")
      (node (ref "F207") (pin "2") (pinfunction "2_2") (pintype "passive"))
      (node (ref "J201") (pin "10") (pinfunction "10_10") (pintype "passive"))
    )
    (net (code "21") (name "/c7_3") (class "Default")
      (node (ref "F307") (pin "2") (pinfunction "2_2") (pintype "passive"))
      (node (ref "J301") (pin "9") (pinfunction "9_9") (pintype "passive"))
    )
    (net (code "22") (name "/c8_1") (class "Default")
      (node (ref "F108") (pin "2") (pinfunction "2_2") (pintype "passive"))
      (node (ref "J101") (pin "10") (pinfunction "10_10") (pintype "passive"))
    )
    (net (code "23") (name "/c8_2") (class "Default")
      (node (ref "F208") (pin "2") (pinfunction "2_2") (pintype "passive"))
      (node (ref "J201") (pin "11") (pinfunction "11_11") (pintype "passive"))
      (node (ref "J201") (pin "12") (pinfunction "12_12") (pintype "passive"))
      (node (ref "J201") (pin "13") (pinfunction "13_13") (pintype "passive"))
    )
    (net (code "24") (name "/c8_3") (class "Default")
      (node (ref "F308") (pin "2") (pinfunction "2_2") (pintype "passive"))
      (node (ref "J301") (pin "10") (pinfunction "10_10") (pintype "passive"))
    )
    (net (code "25") (name "/c9_1") (class "Default")
      (node (ref "F109") (pin "2") (pinfunction "2_2") (pintype "passive"))
      (node (ref "J101") (pin "11") (pinfunction "11_11") (pintype "passive"))
    )
    (net (code "26") (name "/c9_3") (class "Default")
      (node (ref "F309") (pin "2") (pinfunction "2_2") (pintype "passive"))
      (node (ref "J301") (pin "11") (pinfunction "11_11") (pintype "passive"))
    )
    (net (code "27") (name "/c10_1") (class "Default")
      (node (ref "F110") (pin "2") (pinfunction "2_2") (pintype "passive"))
      (node (ref "J101") (pin "12") (pinfunction "12_12") (pintype "passive"))
      (node (ref "J101") (pin "13") (pinfunction "13_13") (pintype "passive"))
    )
    (net (code "28") (name "/c10_3") (class "Default")
      (node (ref "F310") (pin "2") (pinfunction "2_2") (pintype "passive"))
      (node (ref "J301") (pin "12") (pinfunction "12_12") (pintype "passive"))
      (node (ref "J301") (pin "13") (pinfunction "13_13") (pintype "passive"))
    )
    (net (code "29") (name "GND_Slave_1") (class "Default")
      (node (ref "F100") (pin "2") (pinfunction "2_2") (pintype "passive"))
      (node (ref "J101") (pin "1") (pinfunction "1_1") (pintype "passive"))
      (node (ref "NTC101") (pin "1") (pinfunction "2_1") (pintype "passive"))
      (node (ref "NTC102") (pin "1") (pinfunction "2_1") (pintype "passive"))
      (node (ref "NTC103") (pin "1") (pinfunction "2_1") (pintype "passive"))
      (node (ref "NTC104") (pin "1") (pinfunction "2_1") (pintype "passive"))
      (node (ref "NTC105") (pin "2") (pinfunction "2_2") (pintype "passive"))
      (node (ref "NTC106") (pin "2") (pinfunction "2_2") (pintype "passive"))
      (node (ref "NTC107") (pin "2") (pinfunction "2_2") (pintype "passive"))
      (node (ref "NTC108") (pin "2") (pinfunction "2_2") (pintype "passive"))
    )
    (net (code "30") (name "GND_Slave_2") (class "Default")
      (node (ref "F200") (pin "2") (pinfunction "2_2") (pintype "passive"))
      (node (ref "J201") (pin "1") (pinfunction "1_1") (pintype "passive"))
      (node (ref "NTC201") (pin "1") (pinfunction "2_1") (pintype "passive"))
      (node (ref "NTC202") (pin "1") (pinfunction "2_1") (pintype "passive"))
      (node (ref "NTC203") (pin "1") (pinfunction "2_1") (pintype "passive"))
      (node (ref "NTC204") (pin "1") (pinfunction "2_1") (pintype "passive"))
      (node (ref "NTC205") (pin "2") (pinfunction "2_2") (pintype "passive"))
      (node (ref "NTC206") (pin "2") (pinfunction "2_2") (pintype "passive"))
      (node (ref "NTC207") (pin "2") (pinfunction "2_2") (pintype "passive"))
      (node (ref "NTC208") (pin "2") (pinfunction "2_2") (pintype "passive"))
    )
    (net (code "31") (name "GND_Slave_3") (class "Default")
      (node (ref "F300") (pin "2") (pinfunction "2_2") (pintype "passive"))
      (node (ref "J301") (pin "1") (pinfunction "1_1") (pintype "passive"))
      (node (ref "NTC301") (pin "1") (pinfunction "2_1") (pintype "passive"))
      (node (ref "NTC302") (pin "1") (pinfunction "2_1") (pintype "passive"))
      (node (ref "NTC303") (pin "1") (pinfunction "2_1") (pintype "passive"))
      (node (ref "NTC304") (pin "1") (pinfunction "2_1") (pintype "passive"))
      (node (ref "NTC305") (pin "2") (pinfunction "2_2") (pintype "passive"))
      (node (ref "NTC306") (pin "2") (pinfunction "2_2") (pintype "passive"))
      (node (ref "NTC307") (pin "2") (pinfunction "2_2") (pintype "passive"))
      (node (ref "NTC308") (pin "2") (pinfunction "2_2") (pintype "passive"))
    )
    (net (code "32") (name "Net-(F100-Pad1)") (class "Default")
      (node (ref "F100") (pin "1") (pinfunction "1_1") (pintype "passive"))
      (node (ref "TP100") (pin "1") (pinfunction "1_1") (pintype "passive"))
    )
    (net (code "33") (name "Net-(F101-Pad1)") (class "Default")
      (node (ref "F101") (pin "1") (pinfunction "1_1") (pintype "passive"))
      (node (ref "TP101") (pin "1") (pinfunction "1_1") (pintype "passive"))
      (node (ref "TP101*") (pin "1") (pinfunction "1_1") (pintype "passive"))
    )
    (net (code "34") (name "Net-(F102-Pad1)") (class "Default")
      (node (ref "F102") (pin "1") (pinfunction "1_1") (pintype "passive"))
      (node (ref "TP102") (pin "1") (pinfunction "1_1") (pintype "passive"))
      (node (ref "TP102*") (pin "1") (pinfunction "1_1") (pintype "passive"))
    )
    (net (code "35") (name "Net-(F103-Pad1)") (class "Default")
      (node (ref "F103") (pin "1") (pinfunction "1_1") (pintype "passive"))
      (node (ref "TP103") (pin "1") (pinfunction "1_1") (pintype "passive"))
      (node (ref "TP103*") (pin "1") (pinfunction "1_1") (pintype "passive"))
    )
    (net (code "36") (name "Net-(F104-Pad1)") (class "Default")
      (node (ref "F104") (pin "1") (pinfunction "1_1") (pintype "passive"))
      (node (ref "TP104") (pin "1") (pinfunction "1_1") (pintype "passive"))
      (node (ref "TP104*") (pin "1") (pinfunction "1_1") (pintype "passive"))
    )
    (net (code "37") (name "Net-(F105-Pad1)") (class "Default")
      (node (ref "F105") (pin "1") (pinfunction "1_1") (pintype "passive"))
      (node (ref "TP105") (pin "1") (pinfunction "1_1") (pintype "passive"))
      (node (ref "TP105*") (pin "1") (pinfunction "1_1") (pintype "passive"))
    )
    (net (code "38") (name "Net-(F106-Pad1)") (class "Default")
      (node (ref "F106") (pin "1") (pinfunction "1_1") (pintype "passive"))
      (node (ref "TP106") (pin "1") (pinfunction "1_1") (pintype "passive"))
      (node (ref "TP106*") (pin "1") (pinfunction "1_1") (pintype "passive"))
    )
    (net (code "39") (name "Net-(F107-Pad1)") (class "Default")
      (node (ref "F107") (pin "1") (pinfunction "1_1") (pintype "passive"))
      (node (ref "TP107") (pin "1") (pinfunction "1_1") (pintype "passive"))
      (node (ref "TP107*") (pin "1") (pinfunction "1_1") (pintype "passive"))
    )
    (net (code "40") (name "Net-(F108-Pad1)") (class "Default")
      (node (ref "F108") (pin "1") (pinfunction "1_1") (pintype "passive"))
      (node (ref "TP108") (pin "1") (pinfunction "1_1") (pintype "passive"))
      (node (ref "TP108*") (pin "1") (pinfunction "1_1") (pintype "passive"))
    )
    (net (code "41") (name "Net-(F109-Pad1)") (class "Default")
      (node (ref "F109") (pin "1") (pinfunction "1_1") (pintype "passive"))
      (node (ref "TP109") (pin "1") (pinfunction "1_1") (pintype "passive"))
      (node (ref "TP109*") (pin "1") (pinfunction "1_1") (pintype "passive"))
    )
    (net (code "42") (name "Net-(F110-Pad1)") (class "Default")
      (node (ref "F110") (pin "1") (pinfunction "1_1") (pintype "passive"))
      (node (ref "TP110") (pin "1") (pinfunction "1_1") (pintype "passive"))
    )
    (net (code "43") (name "Net-(F200-Pad1)") (class "Default")
      (node (ref "F200") (pin "1") (pinfunction "1_1") (pintype "passive"))
      (node (ref "TP200") (pin "1") (pinfunction "1_1") (pintype "passive"))
    )
    (net (code "44") (name "Net-(F201-Pad1)") (class "Default")
      (node (ref "F201") (pin "1") (pinfunction "1_1") (pintype "passive"))
      (node (ref "TP201") (pin "1") (pinfunction "1_1") (pintype "passive"))
      (node (ref "TP201*") (pin "1") (pinfunction "1_1") (pintype "passive"))
    )
    (net (code "45") (name "Net-(F202-Pad1)") (class "Default")
      (node (ref "F202") (pin "1") (pinfunction "1_1") (pintype "passive"))
      (node (ref "TP202") (pin "1") (pinfunction "1_1") (pintype "passive"))
      (node (ref "TP202*") (pin "1") (pinfunction "1_1") (pintype "passive"))
    )
    (net (code "46") (name "Net-(F203-Pad1)") (class "Default")
      (node (ref "F203") (pin "1") (pinfunction "1_1") (pintype "passive"))
      (node (ref "TP203") (pin "1") (pinfunction "1_1") (pintype "passive"))
      (node (ref "TP203*") (pin "1") (pinfunction "1_1") (pintype "passive"))
    )
    (net (code "47") (name "Net-(F204-Pad1)") (class "Default")
      (node (ref "F204") (pin "1") (pinfunction "1_1") (pintype "passive"))
      (node (ref "TP204") (pin "1") (pinfunction "1_1") (pintype "passive"))
      (node (ref "TP204*") (pin "1") (pinfunction "1_1") (pintype "passive"))
    )
    (net (code "48") (name "Net-(F205-Pad1)") (class "Default")
      (node (ref "F205") (pin "1") (pinfunction "1_1") (pintype "passive"))
      (node (ref "TP205") (pin "1") (pinfunction "1_1") (pintype "passive"))
      (node (ref "TP205*") (pin "1") (pinfunction "1_1") (pintype "passive"))
    )
    (net (code "49") (name "Net-(F206-Pad1)") (class "Default")
      (node (ref "F206") (pin "1") (pinfunction "1_1") (pintype "passive"))
      (node (ref "TP206") (pin "1") (pinfunction "1_1") (pintype "passive"))
      (node (ref "TP206*") (pin "1") (pinfunction "1_1") (pintype "passive"))
    )
    (net (code "50") (name "Net-(F207-Pad1)") (class "Default")
      (node (ref "F207") (pin "1") (pinfunction "1_1") (pintype "passive"))
      (node (ref "TP207") (pin "1") (pinfunction "1_1") (pintype "passive"))
      (node (ref "TP207*") (pin "1") (pinfunction "1_1") (pintype "passive"))
    )
    (net (code "51") (name "Net-(F208-Pad1)") (class "Default")
      (node (ref "F208") (pin "1") (pinfunction "1_1") (pintype "passive"))
      (node (ref "TP208") (pin "1") (pinfunction "1_1") (pintype "passive"))
    )
    (net (code "52") (name "Net-(F300-Pad1)") (class "Default")
      (node (ref "F300") (pin "1") (pinfunction "1_1") (pintype "passive"))
      (node (ref "TP300") (pin "1") (pinfunction "1_1") (pintype "passive"))
    )
    (net (code "53") (name "Net-(F301-Pad1)") (class "Default")
      (node (ref "F301") (pin "1") (pinfunction "1_1") (pintype "passive"))
      (node (ref "TP301") (pin "1") (pinfunction "1_1") (pintype "passive"))
      (node (ref "TP301*") (pin "1") (pinfunction "1_1") (pintype "passive"))
    )
    (net (code "54") (name "Net-(F302-Pad1)") (class "Default")
      (node (ref "F302") (pin "1") (pinfunction "1_1") (pintype "passive"))
      (node (ref "TP302") (pin "1") (pinfunction "1_1") (pintype "passive"))
      (node (ref "TP302*") (pin "1") (pinfunction "1_1") (pintype "passive"))
    )
    (net (code "55") (name "Net-(F303-Pad1)") (class "Default")
      (node (ref "F303") (pin "1") (pinfunction "1_1") (pintype "passive"))
      (node (ref "TP303") (pin "1") (pinfunction "1_1") (pintype "passive"))
      (node (ref "TP303*") (pin "1") (pinfunction "1_1") (pintype "passive"))
    )
    (net (code "56") (name "Net-(F304-Pad1)") (class "Default")
      (node (ref "F304") (pin "1") (pinfunction "1_1") (pintype "passive"))
      (node (ref "TP304") (pin "1") (pinfunction "1_1") (pintype "passive"))
      (node (ref "TP304*") (pin "1") (pinfunction "1_1") (pintype "passive"))
    )
    (net (code "57") (name "Net-(F305-Pad1)") (class "Default")
      (node (ref "F305") (pin "1") (pinfunction "1_1") (pintype "passive"))
      (node (ref "TP305") (pin "1") (pinfunction "1_1") (pintype "passive"))
      (node (ref "TP305*") (pin "1") (pinfunction "1_1") (pintype "passive"))
    )
    (net (code "58") (name "Net-(F306-Pad1)") (class "Default")
      (node (ref "F306") (pin "1") (pinfunction "1_1") (pintype "passive"))
      (node (ref "TP306") (pin "1") (pinfunction "1_1") (pintype "passive"))
      (node (ref "TP306*") (pin "1") (pinfunction "1_1") (pintype "passive"))
    )
    (net (code "59") (name "Net-(F307-Pad1)") (class "Default")
      (node (ref "F307") (pin "1") (pinfunction "1_1") (pintype "passive"))
      (node (ref "TP307") (pin "1") (pinfunction "1_1") (pintype "passive"))
      (node (ref "TP307*") (pin "1") (pinfunction "1_1") (pintype "passive"))
    )
    (net (code "60") (name "Net-(F308-Pad1)") (class "Default")
      (node (ref "F308") (pin "1") (pinfunction "1_1") (pintype "passive"))
      (node (ref "TP308") (pin "1") (pinfunction "1_1") (pintype "passive"))
      (node (ref "TP308*") (pin "1") (pinfunction "1_1") (pintype "passive"))
    )
    (net (code "61") (name "Net-(F309-Pad1)") (class "Default")
      (node (ref "F309") (pin "1") (pinfunction "1_1") (pintype "passive"))
      (node (ref "TP309") (pin "1") (pinfunction "1_1") (pintype "passive"))
      (node (ref "TP309*") (pin "1") (pinfunction "1_1") (pintype "passive"))
    )
    (net (code "62") (name "Net-(F310-Pad1)") (class "Default")
      (node (ref "F310") (pin "1") (pinfunction "1_1") (pintype "passive"))
      (node (ref "TP310") (pin "1") (pinfunction "1_1") (pintype "passive"))
    )
    (net (code "63") (name "Net-(J102-Pad1)") (class "Default")
      (node (ref "J102") (pin "1") (pinfunction "1_1") (pintype "passive"))
      (node (ref "NTC101") (pin "2") (pinfunction "2_2") (pintype "passive"))
    )
    (net (code "64") (name "Net-(J102-Pad2)") (class "Default")
      (node (ref "J102") (pin "2") (pinfunction "2_2") (pintype "passive"))
      (node (ref "NTC102") (pin "2") (pinfunction "2_2") (pintype "passive"))
    )
    (net (code "65") (name "Net-(J102-Pad3)") (class "Default")
      (node (ref "J102") (pin "3") (pinfunction "3_3") (pintype "passive"))
      (node (ref "NTC103") (pin "2") (pinfunction "2_2") (pintype "passive"))
    )
    (net (code "66") (name "Net-(J102-Pad4)") (class "Default")
      (node (ref "J102") (pin "4") (pinfunction "4_4") (pintype "passive"))
      (node (ref "NTC104") (pin "2") (pinfunction "2_2") (pintype "passive"))
    )
    (net (code "67") (name "Net-(J102-Pad5)") (class "Default")
      (node (ref "J102") (pin "5") (pinfunction "5_5") (pintype "passive"))
      (node (ref "NTC105") (pin "1") (pinfunction "2_1") (pintype "passive"))
    )
    (net (code "68") (name "Net-(J102-Pad6)") (class "Default")
      (node (ref "J102") (pin "6") (pinfunction "6_6") (pintype "passive"))
      (node (ref "NTC106") (pin "1") (pinfunction "2_1") (pintype "passive"))
    )
    (net (code "69") (name "Net-(J102-Pad7)") (class "Default")
      (node (ref "J102") (pin "7") (pinfunction "7_7") (pintype "passive"))
      (node (ref "NTC107") (pin "1") (pinfunction "2_1") (pintype "passive"))
    )
    (net (code "70") (name "Net-(J102-Pad8)") (class "Default")
      (node (ref "J102") (pin "8") (pinfunction "8_8") (pintype "passive"))
      (node (ref "NTC108") (pin "1") (pinfunction "2_1") (pintype "passive"))
    )
    (net (code "71") (name "Net-(J202-Pad1)") (class "Default")
      (node (ref "J202") (pin "1") (pinfunction "1_1") (pintype "passive"))
      (node (ref "NTC201") (pin "2") (pinfunction "2_2") (pintype "passive"))
    )
    (net (code "72") (name "Net-(J202-Pad2)") (class "Default")
      (node (ref "J202") (pin "2") (pinfunction "2_2") (pintype "passive"))
      (node (ref "NTC202") (pin "2") (pinfunction "2_2") (pintype "passive"))
    )
    (net (code "73") (name "Net-(J202-Pad3)") (class "Default")
      (node (ref "J202") (pin "3") (pinfunction "3_3") (pintype "passive"))
      (node (ref "NTC203") (pin "2") (pinfunction "2_2") (pintype "passive"))
    )
    (net (code "74") (name "Net-(J202-Pad4)") (class "Default")
      (node (ref "J202") (pin "4") (pinfunction "4_4") (pintype "passive"))
      (node (ref "NTC204") (pin "2") (pinfunction "2_2") (pintype "passive"))
    )
    (net (code "75") (name "Net-(J202-Pad5)") (class "Default")
      (node (ref "J202") (pin "5") (pinfunction "5_5") (pintype "passive"))
      (node (ref "NTC205") (pin "1") (pinfunction "2_1") (pintype "passive"))
    )
    (net (code "76") (name "Net-(J202-Pad6)") (class "Default")
      (node (ref "J202") (pin "6") (pinfunction "6_6") (pintype "passive"))
      (node (ref "NTC206") (pin "1") (pinfunction "2_1") (pintype "passive"))
    )
    (net (code "77") (name "Net-(J202-Pad7)") (class "Default")
      (node (ref "J202") (pin "7") (pinfunction "7_7") (pintype "passive"))
      (node (ref "NTC207") (pin "1") (pinfunction "2_1") (pintype "passive"))
    )
    (net (code "78") (name "Net-(J202-Pad8)") (class "Default")
      (node (ref "J202") (pin "8") (pinfunction "8_8") (pintype "passive"))
      (node (ref "NTC208") (pin "1") (pinfunction "2_1") (pintype "passive"))
    )
    (net (code "79") (name "Net-(J302-Pad1)") (class "Default")
      (node (ref "J302") (pin "1") (pinfunction "1_1") (pintype "passive"))
      (node (ref "NTC301") (pin "2") (pinfunction "2_2") (pintype "passive"))
    )
    (net (code "80") (name "Net-(J302-Pad2)") (class "Default")
      (node (ref "J302") (pin "2") (pinfunction "2_2") (pintype "passive"))
      (node (ref "NTC302") (pin "2") (pinfunction "2_2") (pintype "passive"))
    )
    (net (code "81") (name "Net-(J302-Pad3)") (class "Default")
      (node (ref "J302") (pin "3") (pinfunction "3_3") (pintype "passive"))
      (node (ref "NTC303") (pin "2") (pinfunction "2_2") (pintype "passive"))
    )
    (net (code "82") (name "Net-(J302-Pad4)") (class "Default")
      (node (ref "J302") (pin "4") (pinfunction "4_4") (pintype "passive"))
      (node (ref "NTC304") (pin "2") (pinfunction "2_2") (pintype "passive"))
    )
    (net (code "83") (name "Net-(J302-Pad5)") (class "Default")
      (node (ref "J302") (pin "5") (pinfunction "5_5") (pintype "passive"))
      (node (ref "NTC305") (pin "1") (pinfunction "2_1") (pintype "passive"))
    )
    (net (code "84") (name "Net-(J302-Pad6)") (class "Default")
      (node (ref "J302") (pin "6") (pinfunction "6_6") (pintype "passive"))
      (node (ref "NTC306") (pin "1") (pinfunction "2_1") (pintype "passive"))
    )
    (net (code "85") (name "Net-(J302-Pad7)") (class "Default")
      (node (ref "J302") (pin "7") (pinfunction "7_7") (pintype "passive"))
      (node (ref "NTC307") (pin "1") (pinfunction "2_1") (pintype "passive"))
    )
    (net (code "86") (name "Net-(J302-Pad8)") (class "Default")
      (node (ref "J302") (pin "8") (pinfunction "8_8") (pintype "passive"))
      (node (ref "NTC308") (pin "1") (pinfunction "2_1") (pintype "passive"))
    )
  )
)
